# TopSolarPanel.net
KiCad netlist of a schematic drawn in EAGLE
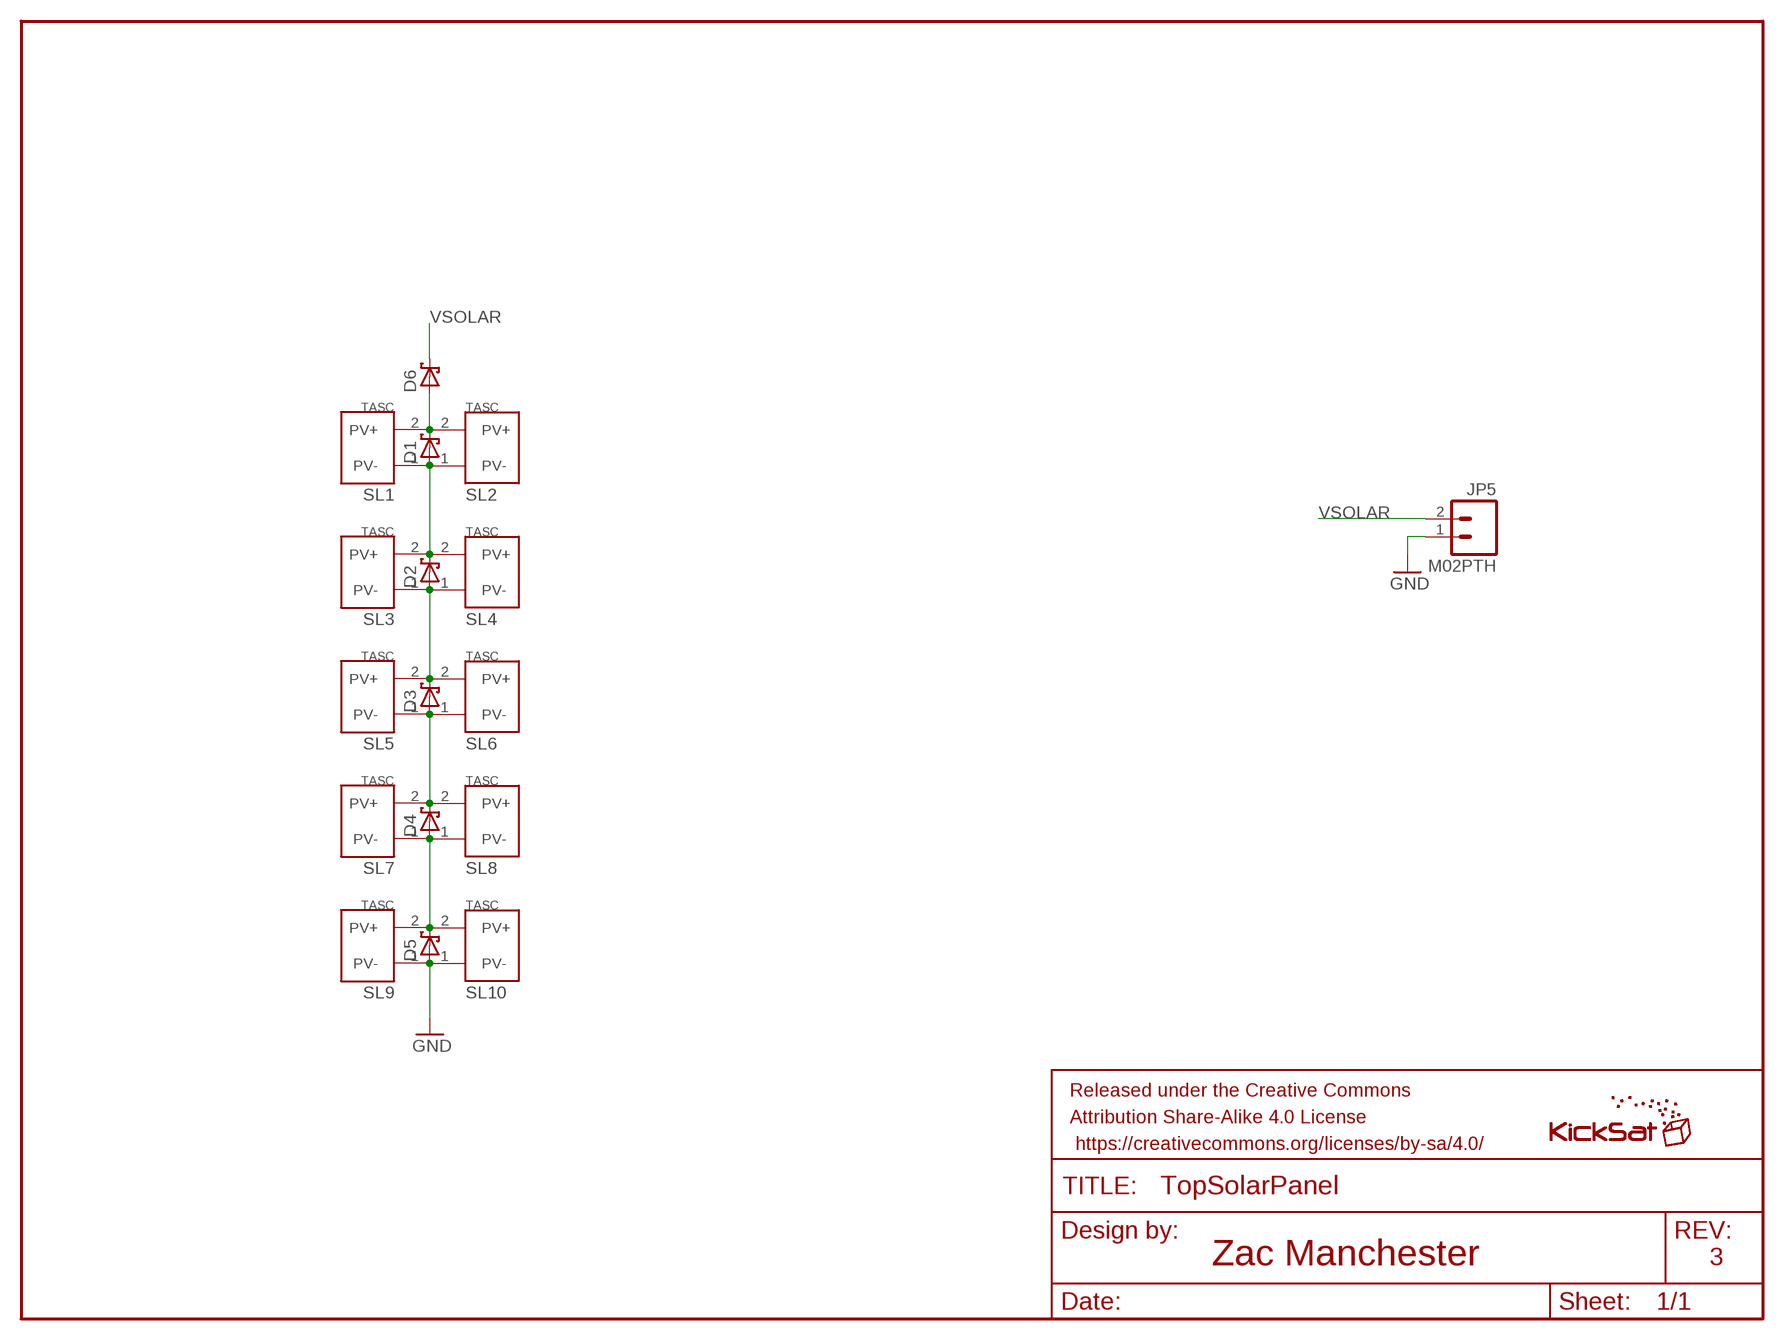
[diagram p0: schematic, sheet 1]

(export (version "E")
  (design (tool "Eeschema 10.0.6"))
  (components
    (comp (ref "D1")
      (value "SB_DIODE")
      (footprint "eagle-import:SB_DIODE")
      (libsource (lib "eagle-import") (part "SB_DIODE"))
    )
    (comp (ref "D2")
      (value "SB_DIODE")
      (footprint "eagle-import:SB_DIODE")
      (libsource (lib "eagle-import") (part "SB_DIODE"))
    )
    (comp (ref "D3")
      (value "SB_DIODE")
      (footprint "eagle-import:SB_DIODE")
      (libsource (lib "eagle-import") (part "SB_DIODE"))
    )
    (comp (ref "D4")
      (value "SB_DIODE")
      (footprint "eagle-import:SB_DIODE")
      (libsource (lib "eagle-import") (part "SB_DIODE"))
    )
    (comp (ref "D5")
      (value "SB_DIODE")
      (footprint "eagle-import:SB_DIODE")
      (libsource (lib "eagle-import") (part "SB_DIODE"))
    )
    (comp (ref "D6")
      (value "SB_DIODE")
      (footprint "eagle-import:SB_DIODE")
      (libsource (lib "eagle-import") (part "SB_DIODE"))
    )
    (comp (ref "FRAME1")
      (value "FRAME-LETTER")
      (footprint "eagle-import:CREATIVE_COMMONS")
      (libsource (lib "eagle-import") (part "FRAME-LETTER"))
    )
    (comp (ref "JP5")
      (value "M02PTH")
      (footprint "eagle-import:1X02")
      (libsource (lib "eagle-import") (part "M02PTH"))
    )
    (comp (ref "SL1")
      (value "SOLAR_CELL")
      (footprint "eagle-import:SOLAR_CELL")
      (libsource (lib "eagle-import") (part "SOLAR_CELL"))
    )
    (comp (ref "SL2")
      (value "SOLAR_CELL")
      (footprint "eagle-import:SOLAR_CELL")
      (libsource (lib "eagle-import") (part "SOLAR_CELL"))
    )
    (comp (ref "SL3")
      (value "SOLAR_CELL")
      (footprint "eagle-import:SOLAR_CELL")
      (libsource (lib "eagle-import") (part "SOLAR_CELL"))
    )
    (comp (ref "SL4")
      (value "SOLAR_CELL")
      (footprint "eagle-import:SOLAR_CELL")
      (libsource (lib "eagle-import") (part "SOLAR_CELL"))
    )
    (comp (ref "SL5")
      (value "SOLAR_CELL")
      (footprint "eagle-import:SOLAR_CELL")
      (libsource (lib "eagle-import") (part "SOLAR_CELL"))
    )
    (comp (ref "SL6")
      (value "SOLAR_CELL")
      (footprint "eagle-import:SOLAR_CELL")
      (libsource (lib "eagle-import") (part "SOLAR_CELL"))
    )
    (comp (ref "SL7")
      (value "SOLAR_CELL")
      (footprint "eagle-import:SOLAR_CELL")
      (libsource (lib "eagle-import") (part "SOLAR_CELL"))
    )
    (comp (ref "SL8")
      (value "SOLAR_CELL")
      (footprint "eagle-import:SOLAR_CELL")
      (libsource (lib "eagle-import") (part "SOLAR_CELL"))
    )
    (comp (ref "SL9")
      (value "SOLAR_CELL")
      (footprint "eagle-import:SOLAR_CELL")
      (libsource (lib "eagle-import") (part "SOLAR_CELL"))
    )
    (comp (ref "SL10")
      (value "SOLAR_CELL")
      (footprint "eagle-import:SOLAR_CELL")
      (libsource (lib "eagle-import") (part "SOLAR_CELL"))
    )
    (comp (ref "U$1")
      (value "KICKSAT_LOGO")
      (footprint "eagle-import:KICKSAT_LOGO")
      (libsource (lib "eagle-import") (part "KICKSAT_LOGO"))
    )
  )
  (nets
    (net (code "1") (name "/VSOLAR") (class "Default")
      (node (ref "D6") (pin "NEG") (pinfunction "NEG_NEG") (pintype "passive"))
      (node (ref "JP5") (pin "2") (pinfunction "2_2") (pintype "passive"))
    )
    (net (code "2") (name "GND") (class "Default")
      (node (ref "D5") (pin "POS") (pinfunction "POS_POS") (pintype "passive"))
      (node (ref "JP5") (pin "1") (pinfunction "1_1") (pintype "passive"))
      (node (ref "SL10") (pin "1") (pinfunction "PV-_1") (pintype "bidirectional"))
      (node (ref "SL9") (pin "1") (pinfunction "PV-_1") (pintype "bidirectional"))
    )
    (net (code "3") (name "Net-(SL1-PV+)") (class "Default")
      (node (ref "D1") (pin "NEG") (pinfunction "NEG_NEG") (pintype "passive"))
      (node (ref "D6") (pin "POS") (pinfunction "POS_POS") (pintype "passive"))
      (node (ref "SL1") (pin "2") (pinfunction "PV+_2") (pintype "bidirectional"))
      (node (ref "SL2") (pin "2") (pinfunction "PV+_2") (pintype "bidirectional"))
    )
    (net (code "4") (name "Net-(SL1-PV-)") (class "Default")
      (node (ref "D1") (pin "POS") (pinfunction "POS_POS") (pintype "passive"))
      (node (ref "D2") (pin "NEG") (pinfunction "NEG_NEG") (pintype "passive"))
      (node (ref "SL1") (pin "1") (pinfunction "PV-_1") (pintype "bidirectional"))
      (node (ref "SL2") (pin "1") (pinfunction "PV-_1") (pintype "bidirectional"))
      (node (ref "SL3") (pin "2") (pinfunction "PV+_2") (pintype "bidirectional"))
      (node (ref "SL4") (pin "2") (pinfunction "PV+_2") (pintype "bidirectional"))
    )
    (net (code "5") (name "Net-(SL3-PV-)") (class "Default")
      (node (ref "D2") (pin "POS") (pinfunction "POS_POS") (pintype "passive"))
      (node (ref "D3") (pin "NEG") (pinfunction "NEG_NEG") (pintype "passive"))
      (node (ref "SL3") (pin "1") (pinfunction "PV-_1") (pintype "bidirectional"))
      (node (ref "SL4") (pin "1") (pinfunction "PV-_1") (pintype "bidirectional"))
      (node (ref "SL5") (pin "2") (pinfunction "PV+_2") (pintype "bidirectional"))
      (node (ref "SL6") (pin "2") (pinfunction "PV+_2") (pintype "bidirectional"))
    )
    (net (code "6") (name "Net-(SL5-PV-)") (class "Default")
      (node (ref "D3") (pin "POS") (pinfunction "POS_POS") (pintype "passive"))
      (node (ref "D4") (pin "NEG") (pinfunction "NEG_NEG") (pintype "passive"))
      (node (ref "SL5") (pin "1") (pinfunction "PV-_1") (pintype "bidirectional"))
      (node (ref "SL6") (pin "1") (pinfunction "PV-_1") (pintype "bidirectional"))
      (node (ref "SL7") (pin "2") (pinfunction "PV+_2") (pintype "bidirectional"))
      (node (ref "SL8") (pin "2") (pinfunction "PV+_2") (pintype "bidirectional"))
    )
    (net (code "7") (name "Net-(SL10-PV+)") (class "Default")
      (node (ref "D4") (pin "POS") (pinfunction "POS_POS") (pintype "passive"))
      (node (ref "D5") (pin "NEG") (pinfunction "NEG_NEG") (pintype "passive"))
      (node (ref "SL10") (pin "2") (pinfunction "PV+_2") (pintype "bidirectional"))
      (node (ref "SL7") (pin "1") (pinfunction "PV-_1") (pintype "bidirectional"))
      (node (ref "SL8") (pin "1") (pinfunction "PV-_1") (pintype "bidirectional"))
      (node (ref "SL9") (pin "2") (pinfunction "PV+_2") (pintype "bidirectional"))
    )
  )
)
